# DSO_IO.net
KiCad netlist of a schematic drawn in Altium Designer
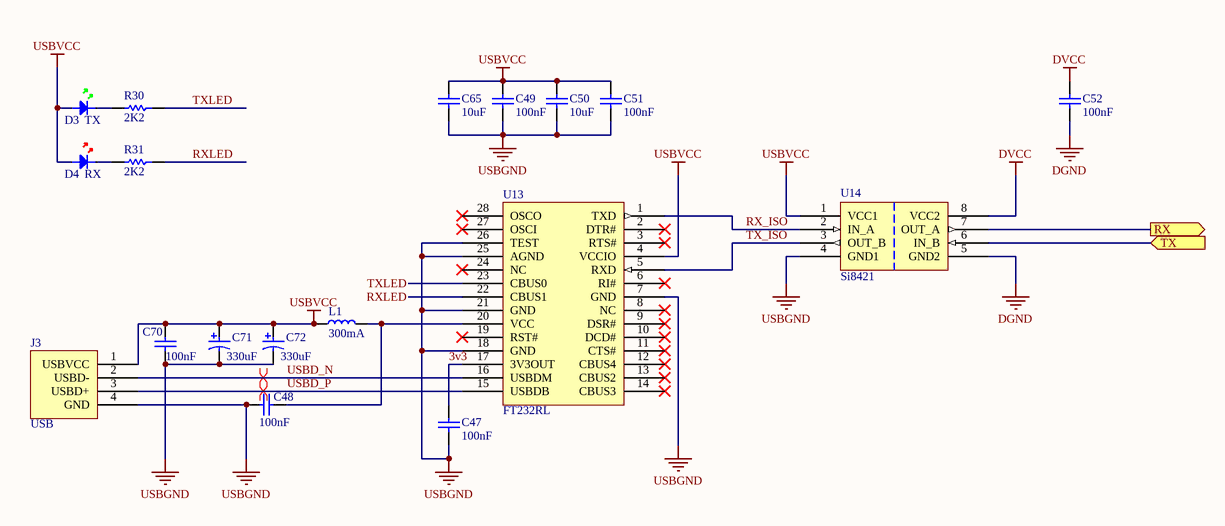
[diagram p0: DSO_IO.SchDoc]

(export (version "E")
  (design (tool "Eeschema 10.0.6"))
  (components
    (comp (ref "C47")
      (value "100nF")
      (footprint "0805C")
      (description "Capacitor")
      (fields (field (name "REVIEWED BY") "RM - 2018/08/05"))
      (libsource (lib "DSO") (part "C"))
    )
    (comp (ref "C48")
      (value "100nF")
      (footprint "0805C")
      (description "Capacitor")
      (fields (field (name "REVIEWED BY") "RM - 2018/08/05"))
      (libsource (lib "DSO") (part "C"))
    )
    (comp (ref "C49")
      (value "100nF")
      (footprint "0805C")
      (description "Capacitor")
      (fields (field (name "REVIEWED BY") "RM - 2018/08/05"))
      (libsource (lib "DSO") (part "C"))
    )
    (comp (ref "C50")
      (value "10uF")
      (footprint "0805C")
      (description "Capacitor")
      (fields (field (name "REVIEWED BY") "RM - 2018/08/05"))
      (libsource (lib "DSO") (part "C"))
    )
    (comp (ref "C51")
      (value "100nF")
      (footprint "0805C")
      (description "Capacitor")
      (fields (field (name "REVIEWED BY") "RM - 2018/08/05"))
      (libsource (lib "DSO") (part "C"))
    )
    (comp (ref "C52")
      (value "100nF")
      (footprint "0805C")
      (description "Capacitor")
      (fields (field (name "REVIEWED BY") "RM - 2018/08/05"))
      (libsource (lib "DSO") (part "C"))
    )
    (comp (ref "C65")
      (value "10uF")
      (footprint "0805C")
      (description "Capacitor")
      (fields (field (name "REVIEWED BY") "RM - 2018/08/05"))
      (libsource (lib "DSO") (part "C"))
    )
    (comp (ref "C70")
      (value "100nF")
      (footprint "0805C")
      (description "Capacitor")
      (fields (field (name "REVIEWED BY") "RM - 2018/08/05"))
      (libsource (lib "DSO") (part "C"))
    )
    (comp (ref "C71")
      (value "TPSD337K006R0050")
      (footprint "CAPMP7344X31-T_V")
      (description "Low ESR, 330 uF, 6.3 V, +/- 10%, -55 to 125 degC, 2-Pin SMD, RoHS, Tape and Reel")
      (fields
        (field (name "CAPACITANCE") "330uF")
        (field (name "MANUFACTURER") "AVX")
        (field (name "VOLTAGE") "6.3VDC")
      )
      (libsource (lib "Altium Content Vault") (part "CAP-P-2"))
    )
    (comp (ref "C72")
      (value "TPSD337K006R0050")
      (footprint "CAPMP7344X31-T_V")
      (description "Low ESR, 330 uF, 6.3 V, +/- 10%, -55 to 125 degC, 2-Pin SMD, RoHS, Tape and Reel")
      (fields
        (field (name "CAPACITANCE") "330uF")
        (field (name "MANUFACTURER") "AVX")
        (field (name "VOLTAGE") "6.3VDC")
      )
      (libsource (lib "Altium Content Vault") (part "CAP-P-2"))
    )
    (comp (ref "D3")
      (value "TX")
      (footprint "0805D-GREEN")
      (description "Light Emitting Diode")
      (fields (field (name "REVIEWED BY") "RM - 2018/08/05"))
      (libsource (lib "DSO") (part "LED GREEN"))
    )
    (comp (ref "D4")
      (value "RX")
      (footprint "0805D-RED")
      (description "Light Emitting Diode")
      (fields (field (name "REVIEWED BY") "RM - 2018/08/05"))
      (libsource (lib "DSO") (part "LED RED"))
    )
    (comp (ref "J3")
      (value "USB")
      (footprint "USBPLUG")
      (description "USB B Type Connector")
      (fields (field (name "REVIEWED BY") "RM - 2018/08/05"))
      (libsource (lib "DSO") (part "USBPLUG"))
    )
    (comp (ref "L1")
      (value "300mA")
      (footprint "0805")
      (description "Inductor")
      (fields (field (name "REVIEWED BY") "RM - 2018/08/05"))
      (libsource (lib "DSO") (part "I"))
    )
    (comp (ref "R30")
      (value "2K2")
      (footprint "0805")
      (description "Resistor")
      (fields (field (name "REVIEWED BY") "RM - 2018/08/05"))
      (libsource (lib "DSO") (part "R"))
    )
    (comp (ref "R31")
      (value "2K2")
      (footprint "0805")
      (description "Resistor")
      (fields (field (name "REVIEWED BY") "RM - 2018/08/05"))
      (libsource (lib "DSO") (part "R"))
    )
    (comp (ref "U13")
      (value "FT232RL")
      (footprint "SSOP-28")
      (description "USB to Serial bridge")
      (fields (field (name "REVIEWED BY") "RM - 2018/08/05"))
      (libsource (lib "DSO") (part "FT232RL"))
    )
    (comp (ref "U14")
      (value "Si8421")
      (footprint "SOIC-8")
      (description "Dual Channel Digital Isolator Both Ways")
      (fields (field (name "REVIEWED BY") "RM - 2018/08/05"))
      (libsource (lib "DSO") (part "Si8421"))
    )
  )
  (nets
    (net (code "1") (name "/3v3") (class "Default")
      (node (ref "C47") (pin "1") (pinfunction "1_1") (pintype "passive"))
      (node (ref "U13") (pin "17") (pinfunction "3V3OUT_17") (pintype "passive"))
    )
    (net (code "2") (name "/RX") (class "Default")
      (node (ref "U14") (pin "7") (pinfunction "OUT_A_7") (pintype "output"))
    )
    (net (code "3") (name "/RXLED") (class "Default")
      (node (ref "R31") (pin "1") (pintype "passive"))
      (node (ref "U13") (pin "22") (pinfunction "CBUS1_22") (pintype "passive"))
    )
    (net (code "4") (name "/RX_ISO") (class "Default")
      (node (ref "U13") (pin "1") (pinfunction "TXD_1") (pintype "output"))
      (node (ref "U14") (pin "2") (pinfunction "IN_A_2") (pintype "input"))
    )
    (net (code "5") (name "/TX") (class "Default")
      (node (ref "U14") (pin "6") (pinfunction "IN_B_6") (pintype "input"))
    )
    (net (code "6") (name "/TXLED") (class "Default")
      (node (ref "R30") (pin "1") (pintype "passive"))
      (node (ref "U13") (pin "23") (pinfunction "CBUS0_23") (pintype "passive"))
    )
    (net (code "7") (name "/TX_ISO") (class "Default")
      (node (ref "U13") (pin "5") (pinfunction "RXD_5") (pintype "input"))
      (node (ref "U14") (pin "3") (pinfunction "OUT_B_3") (pintype "output"))
    )
    (net (code "8") (name "/USBD_N") (class "Default")
      (node (ref "J3") (pin "2") (pinfunction "USBD-_2") (pintype "passive"))
      (node (ref "U13") (pin "16") (pinfunction "USBDM_16") (pintype "passive"))
    )
    (net (code "9") (name "/USBD_P") (class "Default")
      (node (ref "J3") (pin "3") (pinfunction "USBD+_3") (pintype "passive"))
      (node (ref "U13") (pin "15") (pinfunction "USBDB_15") (pintype "passive"))
    )
    (net (code "10") (name "DGND") (class "Default")
      (node (ref "C52") (pin "2") (pinfunction "2_2") (pintype "passive"))
      (node (ref "U14") (pin "5") (pinfunction "GND2_5") (pintype "passive"))
    )
    (net (code "11") (name "DVCC") (class "Default")
      (node (ref "C52") (pin "1") (pinfunction "1_1") (pintype "passive"))
      (node (ref "U14") (pin "8") (pinfunction "VCC2_8") (pintype "passive"))
    )
    (net (code "12") (name "Net-(D3-PadK)") (class "Default")
      (node (ref "D3") (pin "K") (pinfunction "K_K") (pintype "passive"))
      (node (ref "R30") (pin "2") (pintype "passive"))
    )
    (net (code "13") (name "Net-(D4-PadK)") (class "Default")
      (node (ref "D4") (pin "K") (pinfunction "K_K") (pintype "passive"))
      (node (ref "R31") (pin "2") (pintype "passive"))
    )
    (net (code "14") (name "Net-(U13-VCC)") (class "Default")
      (node (ref "C48") (pin "2") (pinfunction "2_2") (pintype "passive"))
      (node (ref "L1") (pin "2") (pinfunction "2_2") (pintype "passive"))
      (node (ref "U13") (pin "20") (pinfunction "VCC_20") (pintype "passive"))
    )
    (net (code "15") (name "USBGND") (class "Default")
      (node (ref "C47") (pin "2") (pinfunction "2_2") (pintype "passive"))
      (node (ref "C48") (pin "1") (pinfunction "1_1") (pintype "passive"))
      (node (ref "C49") (pin "2") (pinfunction "2_2") (pintype "passive"))
      (node (ref "C50") (pin "2") (pinfunction "2_2") (pintype "passive"))
      (node (ref "C51") (pin "2") (pinfunction "2_2") (pintype "passive"))
      (node (ref "C65") (pin "2") (pinfunction "2_2") (pintype "passive"))
      (node (ref "C70") (pin "2") (pinfunction "2_2") (pintype "passive"))
      (node (ref "C71") (pin "2") (pinfunction "2_2") (pintype "passive"))
      (node (ref "C72") (pin "2") (pinfunction "2_2") (pintype "passive"))
      (node (ref "J3") (pin "4") (pinfunction "GND_4") (pintype "passive"))
      (node (ref "U13") (pin "18") (pinfunction "GND_18") (pintype "passive"))
      (node (ref "U13") (pin "21") (pinfunction "GND_21") (pintype "passive"))
      (node (ref "U13") (pin "25") (pinfunction "AGND_25") (pintype "passive"))
      (node (ref "U13") (pin "26") (pinfunction "TEST_26") (pintype "passive"))
      (node (ref "U13") (pin "7") (pinfunction "GND_7") (pintype "passive"))
      (node (ref "U14") (pin "4") (pinfunction "GND1_4") (pintype "passive"))
    )
    (net (code "16") (name "USBVCC") (class "Default")
      (node (ref "C49") (pin "1") (pinfunction "1_1") (pintype "passive"))
      (node (ref "C50") (pin "1") (pinfunction "1_1") (pintype "passive"))
      (node (ref "C51") (pin "1") (pinfunction "1_1") (pintype "passive"))
      (node (ref "C65") (pin "1") (pinfunction "1_1") (pintype "passive"))
      (node (ref "C70") (pin "1") (pinfunction "1_1") (pintype "passive"))
      (node (ref "C71") (pin "1") (pinfunction "1_1") (pintype "passive"))
      (node (ref "C72") (pin "1") (pinfunction "1_1") (pintype "passive"))
      (node (ref "D3") (pin "A") (pinfunction "A_A") (pintype "passive"))
      (node (ref "D4") (pin "A") (pinfunction "A_A") (pintype "passive"))
      (node (ref "J3") (pin "1") (pinfunction "USBVCC_1") (pintype "passive"))
      (node (ref "L1") (pin "1") (pinfunction "1_1") (pintype "passive"))
      (node (ref "U13") (pin "4") (pinfunction "VCCIO_4") (pintype "passive"))
      (node (ref "U14") (pin "1") (pinfunction "VCC1_1") (pintype "passive"))
    )
    (net (code "17") (name "unconnected-(U13-CBUS2-Pad13)") (class "Default")
      (node (ref "U13") (pin "13") (pinfunction "CBUS2_13") (pintype "passive+no_connect"))
    )
    (net (code "18") (name "unconnected-(U13-CBUS3-Pad14)") (class "Default")
      (node (ref "U13") (pin "14") (pinfunction "CBUS3_14") (pintype "passive+no_connect"))
    )
    (net (code "19") (name "unconnected-(U13-CBUS4-Pad12)") (class "Default")
      (node (ref "U13") (pin "12") (pinfunction "CBUS4_12") (pintype "passive+no_connect"))
    )
    (net (code "20") (name "unconnected-(U13-CTS#-Pad11)") (class "Default")
      (node (ref "U13") (pin "11") (pinfunction "CTS#_11") (pintype "passive+no_connect"))
    )
    (net (code "21") (name "unconnected-(U13-DCD#-Pad10)") (class "Default")
      (node (ref "U13") (pin "10") (pinfunction "DCD#_10") (pintype "passive+no_connect"))
    )
    (net (code "22") (name "unconnected-(U13-DSR#-Pad9)") (class "Default")
      (node (ref "U13") (pin "9") (pinfunction "DSR#_9") (pintype "passive+no_connect"))
    )
    (net (code "23") (name "unconnected-(U13-DTR#-Pad2)") (class "Default")
      (node (ref "U13") (pin "2") (pinfunction "DTR#_2") (pintype "passive+no_connect"))
    )
    (net (code "24") (name "unconnected-(U13-NC-Pad8)") (class "Default")
      (node (ref "U13") (pin "8") (pinfunction "NC_8") (pintype "passive+no_connect"))
    )
    (net (code "25") (name "unconnected-(U13-NC-Pad24)") (class "Default")
      (node (ref "U13") (pin "24") (pinfunction "NC_24") (pintype "passive+no_connect"))
    )
    (net (code "26") (name "unconnected-(U13-OSCI-Pad27)") (class "Default")
      (node (ref "U13") (pin "27") (pinfunction "OSCI_27") (pintype "passive+no_connect"))
    )
    (net (code "27") (name "unconnected-(U13-OSCO-Pad28)") (class "Default")
      (node (ref "U13") (pin "28") (pinfunction "OSCO_28") (pintype "passive+no_connect"))
    )
    (net (code "28") (name "unconnected-(U13-RI#-Pad6)") (class "Default")
      (node (ref "U13") (pin "6") (pinfunction "RI#_6") (pintype "passive+no_connect"))
    )
    (net (code "29") (name "unconnected-(U13-RST#-Pad19)") (class "Default")
      (node (ref "U13") (pin "19") (pinfunction "RST#_19") (pintype "passive+no_connect"))
    )
    (net (code "30") (name "unconnected-(U13-RTS#-Pad3)") (class "Default")
      (node (ref "U13") (pin "3") (pinfunction "RTS#_3") (pintype "passive+no_connect"))
    )
  )
)
